# Arduino_UNO_Zeno_Version_2021-05-15.net
KiCad netlist of a schematic drawn in EasyEDA
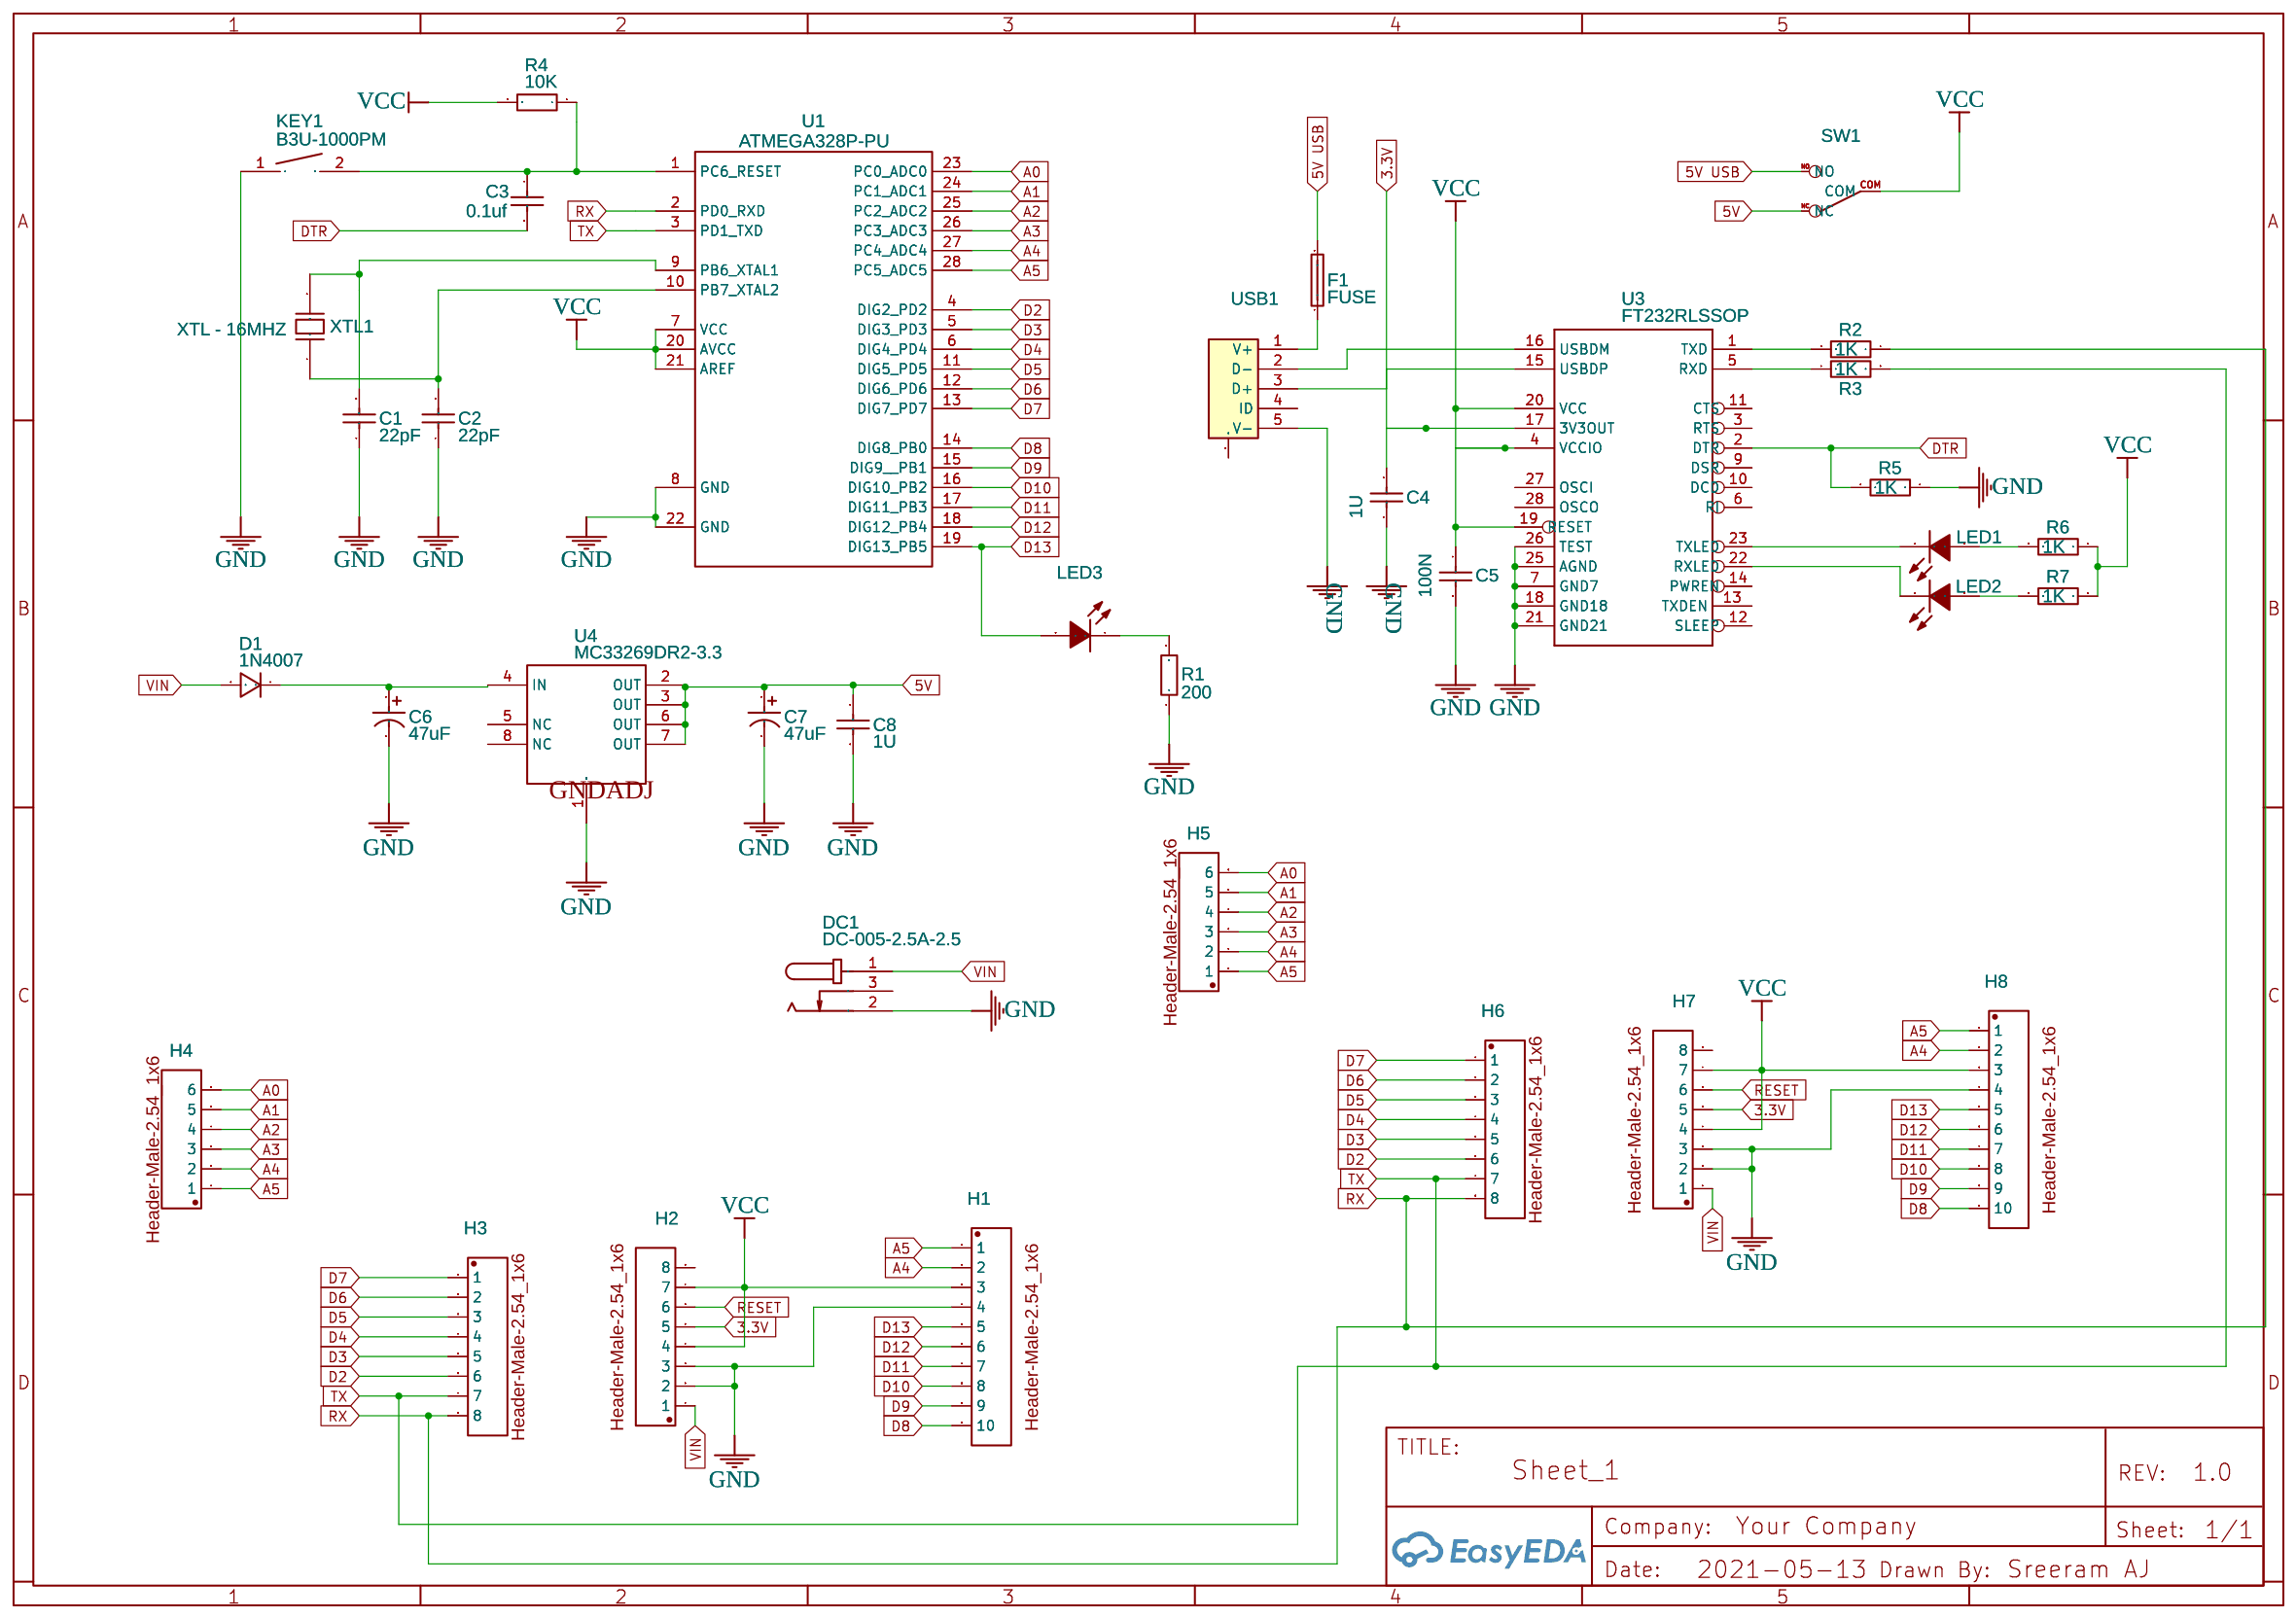
[diagram p0: schematic sheet]

(export (version "E")
  (design (tool "Eeschema 10.0.6"))
  (components
    (comp (ref "C1")
      (value "22pF")
      (fields
        (field (name "BOM_Manufacturer Part") "1206CG220J500NT")
        (field (name "BOM_Supplier Part") "C1896")
      )
      (libsource (lib "") (part "CAPACITOR SMD  22pF 1206_1"))
    )
    (comp (ref "C2")
      (value "22pF")
      (fields
        (field (name "BOM_Manufacturer Part") "1206CG220J500NT")
        (field (name "BOM_Supplier Part") "C1896")
      )
      (libsource (lib "") (part "CAPACITOR SMD  22pF 1206_1"))
    )
    (comp (ref "C3")
      (value "0.1uf")
      (fields
        (field (name "BOM_Manufacturer Part") "1206CG220J500NT")
        (field (name "BOM_Supplier Part") "C1896")
      )
      (libsource (lib "") (part "CAPACITOR SMD  22pF 1206"))
    )
    (comp (ref "C4")
      (value "1U")
      (fields
        (field (name "BOM_Manufacturer Part") "1206CG220J500NT")
        (field (name "BOM_Supplier Part") "C1896")
      )
      (libsource (lib "") (part "CAPACITOR SMD  22pF 1206_1"))
    )
    (comp (ref "C5")
      (value "100N")
      (fields
        (field (name "BOM_Manufacturer Part") "1206CG220J500NT")
        (field (name "BOM_Supplier Part") "C1896")
      )
      (libsource (lib "") (part "CAPACITOR SMD  22pF 1206"))
    )
    (comp (ref "C6")
      (value "47uF")
      (fields
        (field (name "BOM_Manufacturer Part") "EEE-1JA470UP")
        (field (name "BOM_Supplier Part") "PCE3946CT-ND")
      )
      (libsource (lib "") (part "PCE3946CT-ND 47UF 63V SMD CAPACITOR"))
    )
    (comp (ref "C7")
      (value "47uF")
      (fields
        (field (name "BOM_Manufacturer Part") "EEE-1JA470UP")
        (field (name "BOM_Supplier Part") "PCE3946CT-ND")
      )
      (libsource (lib "") (part "PCE3946CT-ND 47UF 63V SMD CAPACITOR"))
    )
    (comp (ref "C8")
      (value "1U")
      (fields
        (field (name "BOM_Manufacturer Part") "1206CG220J500NT")
        (field (name "BOM_Supplier Part") "C1896")
      )
      (libsource (lib "") (part "CAPACITOR SMD  22pF 1206"))
    )
    (comp (ref "D1")
      (value "1N4007")
      (fields (field (name "BOM_Supplier Part") "C126233"))
      (libsource (lib "") (part "DIODE 1N4007 SMD 5X2.56"))
    )
    (comp (ref "DC1")
      (value "DC-005-2.5A-2.5")
      (fields (field (name "BOM_Supplier Part") "C319098"))
      (libsource (lib "") (part "DC-005-2.5A-2.5"))
    )
    (comp (ref "F1")
      (value "FUSE")
      (fields
        (field (name "BOM_Manufacturer Part") "1812L020PR")
        (field (name "BOM_Supplier Part") "C151167")
      )
      (libsource (lib "") (part "1812L020PR"))
    )
    (comp (ref "H1") (value "Header-Male-2.54_1x10") (libsource (lib "") (part "Header-Male-2.54_1x10")))
    (comp (ref "H2") (value "HEADER-MALE-2.54_1X8") (libsource (lib "") (part "HEADER-MALE-2.54_1X8_1")))
    (comp (ref "H3") (value "K") (libsource (lib "") (part "HEADER-MALE-2.54_1X8")))
    (comp (ref "H4") (value "Header-Male-2.54_1x6") (libsource (lib "") (part "Header-Male-2.54_1x6")))
    (comp (ref "H5") (value "Header-Male-2.54_1x6") (libsource (lib "") (part "Header-Male-2.54_1x6")))
    (comp (ref "H6") (value "K") (libsource (lib "") (part "HEADER-MALE-2.54_1X8")))
    (comp (ref "H7") (value "HEADER-MALE-2.54_1X8") (libsource (lib "") (part "HEADER-MALE-2.54_1X8_1")))
    (comp (ref "H8") (value "Header-Male-2.54_1x10") (libsource (lib "") (part "Header-Male-2.54_1x10")))
    (comp (ref "KEY1")
      (value "B3U-1000PM")
      (fields (field (name "BOM_Supplier Part") "C271754"))
      (libsource (lib "") (part "B3U-1000PM"))
    )
    (comp (ref "LED1") (value "LED SMD 0603") (libsource (lib "") (part "LED SMD 0603")))
    (comp (ref "LED2") (value "LED SMD 0603") (libsource (lib "") (part "LED SMD 0603")))
    (comp (ref "LED3") (value "LED SMD 0603") (libsource (lib "") (part "LED SMD 0603_1")))
    (comp (ref "R1")
      (value "200")
      (fields
        (field (name "BOM_Manufacturer Part") "RS-03K102JT")
        (field (name "BOM_Supplier Part") "C73797")
      )
      (libsource (lib "") (part "1k Resistor SMD 0603 (C73797)"))
    )
    (comp (ref "R2")
      (value "1K")
      (fields
        (field (name "BOM_Manufacturer Part") "RS-03K102JT")
        (field (name "BOM_Supplier Part") "C73797")
      )
      (libsource (lib "") (part "1k Resistor SMD 0603 (C73797)_1"))
    )
    (comp (ref "R3")
      (value "1K")
      (fields
        (field (name "BOM_Manufacturer Part") "RS-03K102JT")
        (field (name "BOM_Supplier Part") "C73797")
      )
      (libsource (lib "") (part "1k Resistor SMD 0603 (C73797)_2"))
    )
    (comp (ref "R4")
      (value "10K")
      (fields
        (field (name "BOM_Manufacturer Part") "RS-03K102JT")
        (field (name "BOM_Supplier Part") "C73797")
      )
      (libsource (lib "") (part "1k Resistor SMD 0603 (C73797)_1"))
    )
    (comp (ref "R5")
      (value "1K")
      (fields
        (field (name "BOM_Manufacturer Part") "RS-03K102JT")
        (field (name "BOM_Supplier Part") "C73797")
      )
      (libsource (lib "") (part "1k Resistor SMD 0603 (C73797)_1"))
    )
    (comp (ref "R6")
      (value "1K")
      (fields
        (field (name "BOM_Manufacturer Part") "RS-03K102JT")
        (field (name "BOM_Supplier Part") "C73797")
      )
      (libsource (lib "") (part "1k Resistor SMD 0603 (C73797)_1"))
    )
    (comp (ref "R7")
      (value "1K")
      (fields
        (field (name "BOM_Manufacturer Part") "RS-03K102JT")
        (field (name "BOM_Supplier Part") "C73797")
      )
      (libsource (lib "") (part "1k Resistor SMD 0603 (C73797)_1"))
    )
    (comp (ref "SW1") (value "SW_SLIDE") (libsource (lib "") (part "SW_SLIDE")))
    (comp (ref "U1")
      (value "ATMEGA328P-PU")
      (fields (field (name "BOM_Supplier Part") "C33901"))
      (libsource (lib "") (part "ATMEGA328P-PU"))
    )
    (comp (ref "U3") (value "FT232RLSSOP") (libsource (lib "") (part "FT232RLSSOP")))
    (comp (ref "U4")
      (value "MC33269DR2-3.3")
      (fields (field (name "BOM_Supplier Part") "C7301"))
      (libsource (lib "") (part "MC33269DR2-3.3"))
    )
    (comp (ref "USB1")
      (value "micro USBFemale")
      (fields (field (name "BOM_Supplier Part") "C10418"))
      (libsource (lib "") (part "micro USBFemale"))
    )
    (comp (ref "XTL1")
      (value "XTL - 16MHZ")
      (fields (field (name "BOM_Manufacturer Part") "NTPL INSIDE"))
      (libsource (lib "") (part "XTL - 16MHZ"))
    )
  )
  (nets
    (net (code "1") (name "3.3V") (class "Default")
      (node (ref "C4") (pin "2") (pinfunction "2_2") (pintype "input"))
      (node (ref "H2") (pin "5") (pinfunction "5_5") (pintype "unspecified"))
      (node (ref "H7") (pin "5") (pinfunction "5_5") (pintype "unspecified"))
      (node (ref "U3") (pin "17") (pinfunction "3V3OUT_17") (pintype "output"))
    )
    (net (code "2") (name "5V") (class "Default")
      (node (ref "C7") (pin "1") (pinfunction "1_1") (pintype "input"))
      (node (ref "C8") (pin "1") (pinfunction "1_1") (pintype "input"))
      (node (ref "SW1") (pin "NC") (pinfunction "NC_NC") (pintype "unspecified"))
      (node (ref "U4") (pin "2") (pinfunction "OUT_2") (pintype "passive"))
      (node (ref "U4") (pin "3") (pinfunction "OUT_3") (pintype "passive"))
      (node (ref "U4") (pin "6") (pinfunction "OUT_6") (pintype "passive"))
      (node (ref "U4") (pin "7") (pinfunction "OUT_7") (pintype "passive"))
    )
    (net (code "3") (name "5V USB") (class "Default")
      (node (ref "F1") (pin "2") (pinfunction "2_2") (pintype "unspecified"))
      (node (ref "SW1") (pin "NO") (pinfunction "NO_NO") (pintype "unspecified"))
    )
    (net (code "4") (name "A0") (class "Default")
      (node (ref "H4") (pin "6") (pinfunction "6_6") (pintype "unspecified"))
      (node (ref "H5") (pin "6") (pinfunction "6_6") (pintype "unspecified"))
      (node (ref "U1") (pin "23") (pinfunction "PC0_ADC0_23") (pintype "bidirectional"))
    )
    (net (code "5") (name "A1") (class "Default")
      (node (ref "H4") (pin "5") (pinfunction "5_5") (pintype "unspecified"))
      (node (ref "H5") (pin "5") (pinfunction "5_5") (pintype "unspecified"))
      (node (ref "U1") (pin "24") (pinfunction "PC1_ADC1_24") (pintype "bidirectional"))
    )
    (net (code "6") (name "A2") (class "Default")
      (node (ref "H4") (pin "4") (pinfunction "4_4") (pintype "unspecified"))
      (node (ref "H5") (pin "4") (pinfunction "4_4") (pintype "unspecified"))
      (node (ref "U1") (pin "25") (pinfunction "PC2_ADC2_25") (pintype "bidirectional"))
    )
    (net (code "7") (name "A3") (class "Default")
      (node (ref "H4") (pin "3") (pinfunction "3_3") (pintype "unspecified"))
      (node (ref "H5") (pin "3") (pinfunction "3_3") (pintype "unspecified"))
      (node (ref "U1") (pin "26") (pinfunction "PC3_ADC3_26") (pintype "bidirectional"))
    )
    (net (code "8") (name "A4") (class "Default")
      (node (ref "H1") (pin "2") (pinfunction "2_2") (pintype "unspecified"))
      (node (ref "H4") (pin "2") (pinfunction "2_2") (pintype "unspecified"))
      (node (ref "H5") (pin "2") (pinfunction "2_2") (pintype "unspecified"))
      (node (ref "H8") (pin "2") (pinfunction "2_2") (pintype "unspecified"))
      (node (ref "U1") (pin "27") (pinfunction "PC4_ADC4_27") (pintype "bidirectional"))
    )
    (net (code "9") (name "A5") (class "Default")
      (node (ref "H1") (pin "1") (pinfunction "1_1") (pintype "unspecified"))
      (node (ref "H4") (pin "1") (pinfunction "1_1") (pintype "unspecified"))
      (node (ref "H5") (pin "1") (pinfunction "1_1") (pintype "unspecified"))
      (node (ref "H8") (pin "1") (pinfunction "1_1") (pintype "unspecified"))
      (node (ref "U1") (pin "28") (pinfunction "PC5_ADC5_28") (pintype "bidirectional"))
    )
    (net (code "10") (name "D2") (class "Default")
      (node (ref "H3") (pin "6") (pinfunction "6_6") (pintype "unspecified"))
      (node (ref "H6") (pin "6") (pinfunction "6_6") (pintype "unspecified"))
      (node (ref "U1") (pin "4") (pinfunction "DIG2_PD2_4") (pintype "bidirectional"))
    )
    (net (code "11") (name "D3") (class "Default")
      (node (ref "H3") (pin "5") (pinfunction "5_5") (pintype "unspecified"))
      (node (ref "H6") (pin "5") (pinfunction "5_5") (pintype "unspecified"))
      (node (ref "U1") (pin "5") (pinfunction "DIG3_PD3_5") (pintype "bidirectional"))
    )
    (net (code "12") (name "D4") (class "Default")
      (node (ref "H3") (pin "4") (pinfunction "4_4") (pintype "unspecified"))
      (node (ref "H6") (pin "4") (pinfunction "4_4") (pintype "unspecified"))
      (node (ref "U1") (pin "6") (pinfunction "DIG4_PD4_6") (pintype "bidirectional"))
    )
    (net (code "13") (name "D5") (class "Default")
      (node (ref "H3") (pin "3") (pinfunction "3_3") (pintype "unspecified"))
      (node (ref "H6") (pin "3") (pinfunction "3_3") (pintype "unspecified"))
      (node (ref "U1") (pin "11") (pinfunction "DIG5_PD5_11") (pintype "bidirectional"))
    )
    (net (code "14") (name "D6") (class "Default")
      (node (ref "H3") (pin "2") (pinfunction "2_2") (pintype "unspecified"))
      (node (ref "H6") (pin "2") (pinfunction "2_2") (pintype "unspecified"))
      (node (ref "U1") (pin "12") (pinfunction "DIG6_PD6_12") (pintype "bidirectional"))
    )
    (net (code "15") (name "D7") (class "Default")
      (node (ref "H3") (pin "1") (pinfunction "1_1") (pintype "unspecified"))
      (node (ref "H6") (pin "1") (pinfunction "1_1") (pintype "unspecified"))
      (node (ref "U1") (pin "13") (pinfunction "DIG7_PD7_13") (pintype "bidirectional"))
    )
    (net (code "16") (name "D8") (class "Default")
      (node (ref "H1") (pin "10") (pinfunction "10_10") (pintype "unspecified"))
      (node (ref "H8") (pin "10") (pinfunction "10_10") (pintype "unspecified"))
      (node (ref "U1") (pin "14") (pinfunction "DIG8_PB0_14") (pintype "bidirectional"))
    )
    (net (code "17") (name "D9") (class "Default")
      (node (ref "H1") (pin "9") (pinfunction "9_9") (pintype "unspecified"))
      (node (ref "H8") (pin "9") (pinfunction "9_9") (pintype "unspecified"))
      (node (ref "U1") (pin "15") (pinfunction "DIG9__PB1_15") (pintype "bidirectional"))
    )
    (net (code "18") (name "D10") (class "Default")
      (node (ref "H1") (pin "8") (pinfunction "8_8") (pintype "unspecified"))
      (node (ref "H8") (pin "8") (pinfunction "8_8") (pintype "unspecified"))
      (node (ref "U1") (pin "16") (pinfunction "DIG10_PB2_16") (pintype "bidirectional"))
    )
    (net (code "19") (name "D11") (class "Default")
      (node (ref "H1") (pin "7") (pinfunction "7_7") (pintype "unspecified"))
      (node (ref "H8") (pin "7") (pinfunction "7_7") (pintype "unspecified"))
      (node (ref "U1") (pin "17") (pinfunction "DIG11_PB3_17") (pintype "bidirectional"))
    )
    (net (code "20") (name "D12") (class "Default")
      (node (ref "H1") (pin "6") (pinfunction "6_6") (pintype "unspecified"))
      (node (ref "H8") (pin "6") (pinfunction "6_6") (pintype "unspecified"))
      (node (ref "U1") (pin "18") (pinfunction "DIG12_PB4_18") (pintype "bidirectional"))
    )
    (net (code "21") (name "D13") (class "Default")
      (node (ref "H1") (pin "5") (pinfunction "5_5") (pintype "unspecified"))
      (node (ref "H8") (pin "5") (pinfunction "5_5") (pintype "unspecified"))
      (node (ref "LED3") (pin "2") (pinfunction "A_2") (pintype "unspecified"))
      (node (ref "U1") (pin "19") (pinfunction "DIG13_PB5_19") (pintype "bidirectional"))
    )
    (net (code "22") (name "DTR") (class "Default")
      (node (ref "C3") (pin "2") (pinfunction "2_2") (pintype "input"))
      (node (ref "R5") (pin "2") (pinfunction "2_2") (pintype "input"))
      (node (ref "U3") (pin "2") (pinfunction "DTR_2") (pintype "output"))
    )
    (net (code "23") (name "GND") (class "Default")
      (node (ref "C1") (pin "1") (pinfunction "1_1") (pintype "input"))
      (node (ref "C2") (pin "1") (pinfunction "1_1") (pintype "input"))
      (node (ref "C4") (pin "1") (pinfunction "1_1") (pintype "input"))
      (node (ref "C5") (pin "2") (pinfunction "2_2") (pintype "input"))
      (node (ref "C6") (pin "2") (pinfunction "2_2") (pintype "input"))
      (node (ref "C7") (pin "2") (pinfunction "2_2") (pintype "input"))
      (node (ref "C8") (pin "2") (pinfunction "2_2") (pintype "input"))
      (node (ref "DC1") (pin "2") (pinfunction "2_2") (pintype "unspecified"))
      (node (ref "H1") (pin "4") (pinfunction "4_4") (pintype "unspecified"))
      (node (ref "H2") (pin "2") (pinfunction "2_2") (pintype "unspecified"))
      (node (ref "H2") (pin "3") (pinfunction "3_3") (pintype "unspecified"))
      (node (ref "H7") (pin "2") (pinfunction "2_2") (pintype "unspecified"))
      (node (ref "H7") (pin "3") (pinfunction "3_3") (pintype "unspecified"))
      (node (ref "H8") (pin "4") (pinfunction "4_4") (pintype "unspecified"))
      (node (ref "KEY1") (pin "1") (pinfunction "1_1") (pintype "input"))
      (node (ref "R1") (pin "1") (pinfunction "1_1") (pintype "input"))
      (node (ref "R5") (pin "1") (pinfunction "1_1") (pintype "input"))
      (node (ref "U1") (pin "22") (pinfunction "GND_22") (pintype "passive"))
      (node (ref "U1") (pin "8") (pinfunction "GND_8") (pintype "passive"))
      (node (ref "U3") (pin "18") (pinfunction "GND18_18") (pintype "passive"))
      (node (ref "U3") (pin "21") (pinfunction "GND21_21") (pintype "passive"))
      (node (ref "U3") (pin "25") (pinfunction "AGND_25") (pintype "passive"))
      (node (ref "U3") (pin "26") (pinfunction "TEST_26") (pintype "input"))
      (node (ref "U3") (pin "7") (pinfunction "GND7_7") (pintype "passive"))
      (node (ref "U4") (pin "1") (pinfunction "GNDADJ_1") (pintype "passive"))
      (node (ref "USB1") (pin "5") (pinfunction "V-_5") (pintype "unspecified"))
    )
    (net (code "24") (name "Net-(LED1-A)") (class "Default")
      (node (ref "LED1") (pin "2") (pinfunction "A_2") (pintype "unspecified"))
      (node (ref "R6") (pin "2") (pinfunction "2_2") (pintype "input"))
    )
    (net (code "25") (name "Net-(LED1-K)") (class "Default")
      (node (ref "LED1") (pin "1") (pinfunction "K_1") (pintype "unspecified"))
      (node (ref "U3") (pin "23") (pinfunction "TXLED_23") (pintype "input"))
    )
    (net (code "26") (name "Net-(LED2-A)") (class "Default")
      (node (ref "LED2") (pin "2") (pinfunction "A_2") (pintype "unspecified"))
      (node (ref "R7") (pin "2") (pinfunction "2_2") (pintype "input"))
    )
    (net (code "27") (name "Net-(LED2-K)") (class "Default")
      (node (ref "LED2") (pin "1") (pinfunction "K_1") (pintype "unspecified"))
      (node (ref "U3") (pin "22") (pinfunction "RXLED_22") (pintype "input"))
    )
    (net (code "28") (name "Net-(LED3-K)") (class "Default")
      (node (ref "LED3") (pin "1") (pinfunction "K_1") (pintype "unspecified"))
      (node (ref "R1") (pin "2") (pinfunction "2_2") (pintype "input"))
    )
    (net (code "29") (name "Net-(U1-PB6_XTAL1)") (class "Default")
      (node (ref "C1") (pin "2") (pinfunction "2_2") (pintype "input"))
      (node (ref "U1") (pin "9") (pinfunction "PB6_XTAL1_9") (pintype "bidirectional"))
      (node (ref "XTL1") (pin "2") (pinfunction "2_2") (pintype "unspecified"))
    )
    (net (code "30") (name "Net-(U1-PB7_XTAL2)") (class "Default")
      (node (ref "C2") (pin "2") (pinfunction "2_2") (pintype "input"))
      (node (ref "U1") (pin "10") (pinfunction "PB7_XTAL2_10") (pintype "bidirectional"))
      (node (ref "XTL1") (pin "1") (pinfunction "1_1") (pintype "unspecified"))
    )
    (net (code "31") (name "Net-(U1-PC6_RESET)") (class "Default")
      (node (ref "C3") (pin "1") (pinfunction "1_1") (pintype "input"))
      (node (ref "KEY1") (pin "2") (pinfunction "2_2") (pintype "input"))
      (node (ref "R4") (pin "1") (pinfunction "1_1") (pintype "input"))
      (node (ref "U1") (pin "1") (pinfunction "PC6_RESET_1") (pintype "bidirectional"))
    )
    (net (code "32") (name "Net-(U3-RXD)") (class "Default")
      (node (ref "R3") (pin "1") (pinfunction "1_1") (pintype "input"))
      (node (ref "U3") (pin "5") (pinfunction "RXD_5") (pintype "input"))
    )
    (net (code "33") (name "Net-(U3-TXD)") (class "Default")
      (node (ref "R2") (pin "2") (pinfunction "2_2") (pintype "input"))
      (node (ref "U3") (pin "1") (pinfunction "TXD_1") (pintype "output"))
    )
    (net (code "34") (name "Net-(U3-USBDM)") (class "Default")
      (node (ref "U3") (pin "16") (pinfunction "USBDM_16") (pintype "unspecified"))
      (node (ref "USB1") (pin "2") (pinfunction "D-_2") (pintype "unspecified"))
    )
    (net (code "35") (name "Net-(U3-USBDP)") (class "Default")
      (node (ref "U3") (pin "15") (pinfunction "USBDP_15") (pintype "unspecified"))
      (node (ref "USB1") (pin "3") (pinfunction "D+_3") (pintype "unspecified"))
    )
    (net (code "36") (name "Net-(U4-IN)") (class "Default")
      (node (ref "C6") (pin "1") (pinfunction "1_1") (pintype "input"))
      (node (ref "D1") (pin "1") (pinfunction "1_1") (pintype "unspecified"))
      (node (ref "U4") (pin "4") (pinfunction "IN_4") (pintype "passive"))
    )
    (net (code "37") (name "Net-(USB1-V+)") (class "Default")
      (node (ref "F1") (pin "1") (pinfunction "1_1") (pintype "unspecified"))
      (node (ref "USB1") (pin "1") (pinfunction "V+_1") (pintype "unspecified"))
    )
    (net (code "38") (name "RESET") (class "Default")
      (node (ref "H2") (pin "6") (pinfunction "6_6") (pintype "unspecified"))
      (node (ref "H7") (pin "6") (pinfunction "6_6") (pintype "unspecified"))
    )
    (net (code "39") (name "RX") (class "Default")
      (node (ref "H3") (pin "8") (pinfunction "8_8") (pintype "unspecified"))
      (node (ref "H6") (pin "8") (pinfunction "8_8") (pintype "unspecified"))
      (node (ref "R2") (pin "1") (pinfunction "1_1") (pintype "input"))
      (node (ref "U1") (pin "2") (pinfunction "PD0_RXD_2") (pintype "bidirectional"))
    )
    (net (code "40") (name "TX") (class "Default")
      (node (ref "H3") (pin "7") (pinfunction "7_7") (pintype "unspecified"))
      (node (ref "H6") (pin "7") (pinfunction "7_7") (pintype "unspecified"))
      (node (ref "R3") (pin "2") (pinfunction "2_2") (pintype "input"))
      (node (ref "U1") (pin "3") (pinfunction "PD1_TXD_3") (pintype "bidirectional"))
    )
    (net (code "41") (name "VCC") (class "Default")
      (node (ref "C5") (pin "1") (pinfunction "1_1") (pintype "input"))
      (node (ref "H1") (pin "3") (pinfunction "3_3") (pintype "unspecified"))
      (node (ref "H2") (pin "4") (pinfunction "4_4") (pintype "unspecified"))
      (node (ref "H2") (pin "7") (pinfunction "7_7") (pintype "unspecified"))
      (node (ref "H7") (pin "4") (pinfunction "4_4") (pintype "unspecified"))
      (node (ref "H7") (pin "7") (pinfunction "7_7") (pintype "unspecified"))
      (node (ref "H8") (pin "3") (pinfunction "3_3") (pintype "unspecified"))
      (node (ref "R4") (pin "2") (pinfunction "2_2") (pintype "input"))
      (node (ref "R6") (pin "1") (pinfunction "1_1") (pintype "input"))
      (node (ref "R7") (pin "1") (pinfunction "1_1") (pintype "input"))
      (node (ref "SW1") (pin "COM") (pinfunction "COM_COM") (pintype "unspecified"))
      (node (ref "U1") (pin "20") (pinfunction "AVCC_20") (pintype "passive"))
      (node (ref "U1") (pin "21") (pinfunction "AREF_21") (pintype "passive"))
      (node (ref "U1") (pin "7") (pinfunction "VCC_7") (pintype "passive"))
      (node (ref "U3") (pin "19") (pinfunction "RESET_19") (pintype "input"))
      (node (ref "U3") (pin "20") (pinfunction "VCC_20") (pintype "passive"))
      (node (ref "U3") (pin "4") (pinfunction "VCCIO_4") (pintype "passive"))
    )
    (net (code "42") (name "VIN") (class "Default")
      (node (ref "D1") (pin "2") (pinfunction "2_2") (pintype "unspecified"))
      (node (ref "DC1") (pin "1") (pinfunction "1_1") (pintype "unspecified"))
      (node (ref "H2") (pin "1") (pinfunction "1_1") (pintype "unspecified"))
      (node (ref "H7") (pin "1") (pinfunction "1_1") (pintype "unspecified"))
    )
    (net (code "43") (name "unconnected-(DC1-Pad3)") (class "Default")
      (node (ref "DC1") (pin "3") (pinfunction "3_3") (pintype "unspecified"))
    )
    (net (code "44") (name "unconnected-(H2-Pad8)") (class "Default")
      (node (ref "H2") (pin "8") (pinfunction "8_8") (pintype "unspecified"))
    )
    (net (code "45") (name "unconnected-(H7-Pad8)") (class "Default")
      (node (ref "H7") (pin "8") (pinfunction "8_8") (pintype "unspecified"))
    )
    (net (code "46") (name "unconnected-(U3-CTS-Pad11)") (class "Default")
      (node (ref "U3") (pin "11") (pinfunction "CTS_11") (pintype "input"))
    )
    (net (code "47") (name "unconnected-(U3-DCD-Pad10)") (class "Default")
      (node (ref "U3") (pin "10") (pinfunction "DCD_10") (pintype "input"))
    )
    (net (code "48") (name "unconnected-(U3-DSR-Pad9)") (class "Default")
      (node (ref "U3") (pin "9") (pinfunction "DSR_9") (pintype "input"))
    )
    (net (code "49") (name "unconnected-(U3-OSCI-Pad27)") (class "Default")
      (node (ref "U3") (pin "27") (pinfunction "OSCI_27") (pintype "input"))
    )
    (net (code "50") (name "unconnected-(U3-OSCO-Pad28)") (class "Default")
      (node (ref "U3") (pin "28") (pinfunction "OSCO_28") (pintype "output"))
    )
    (net (code "51") (name "unconnected-(U3-PWREN-Pad14)") (class "Default")
      (node (ref "U3") (pin "14") (pinfunction "PWREN_14") (pintype "input"))
    )
    (net (code "52") (name "unconnected-(U3-RI-Pad6)") (class "Default")
      (node (ref "U3") (pin "6") (pinfunction "RI_6") (pintype "input"))
    )
    (net (code "53") (name "unconnected-(U3-RTS-Pad3)") (class "Default")
      (node (ref "U3") (pin "3") (pinfunction "RTS_3") (pintype "output"))
    )
    (net (code "54") (name "unconnected-(U3-SLEEP-Pad12)") (class "Default")
      (node (ref "U3") (pin "12") (pinfunction "SLEEP_12") (pintype "input"))
    )
    (net (code "55") (name "unconnected-(U3-TXDEN-Pad13)") (class "Default")
      (node (ref "U3") (pin "13") (pinfunction "TXDEN_13") (pintype "input"))
    )
    (net (code "56") (name "unconnected-(U4-NC-Pad5)") (class "Default")
      (node (ref "U4") (pin "5") (pinfunction "NC_5") (pintype "unspecified"))
    )
    (net (code "57") (name "unconnected-(U4-NC-Pad8)") (class "Default")
      (node (ref "U4") (pin "8") (pinfunction "NC_8") (pintype "unspecified"))
    )
    (net (code "58") (name "unconnected-(USB1-ID-Pad4)") (class "Default")
      (node (ref "USB1") (pin "4") (pinfunction "ID_4") (pintype "unspecified"))
    )
    (net (code "59") (name "unconnected-(USB1-MTN-Pad0)") (class "Default")
      (node (ref "USB1") (pin "0") (pinfunction "MTN_0") (pintype "input"))
    )
  )
)
